# WGA_IR_P.net
KiCad netlist of a schematic drawn in Altium Designer
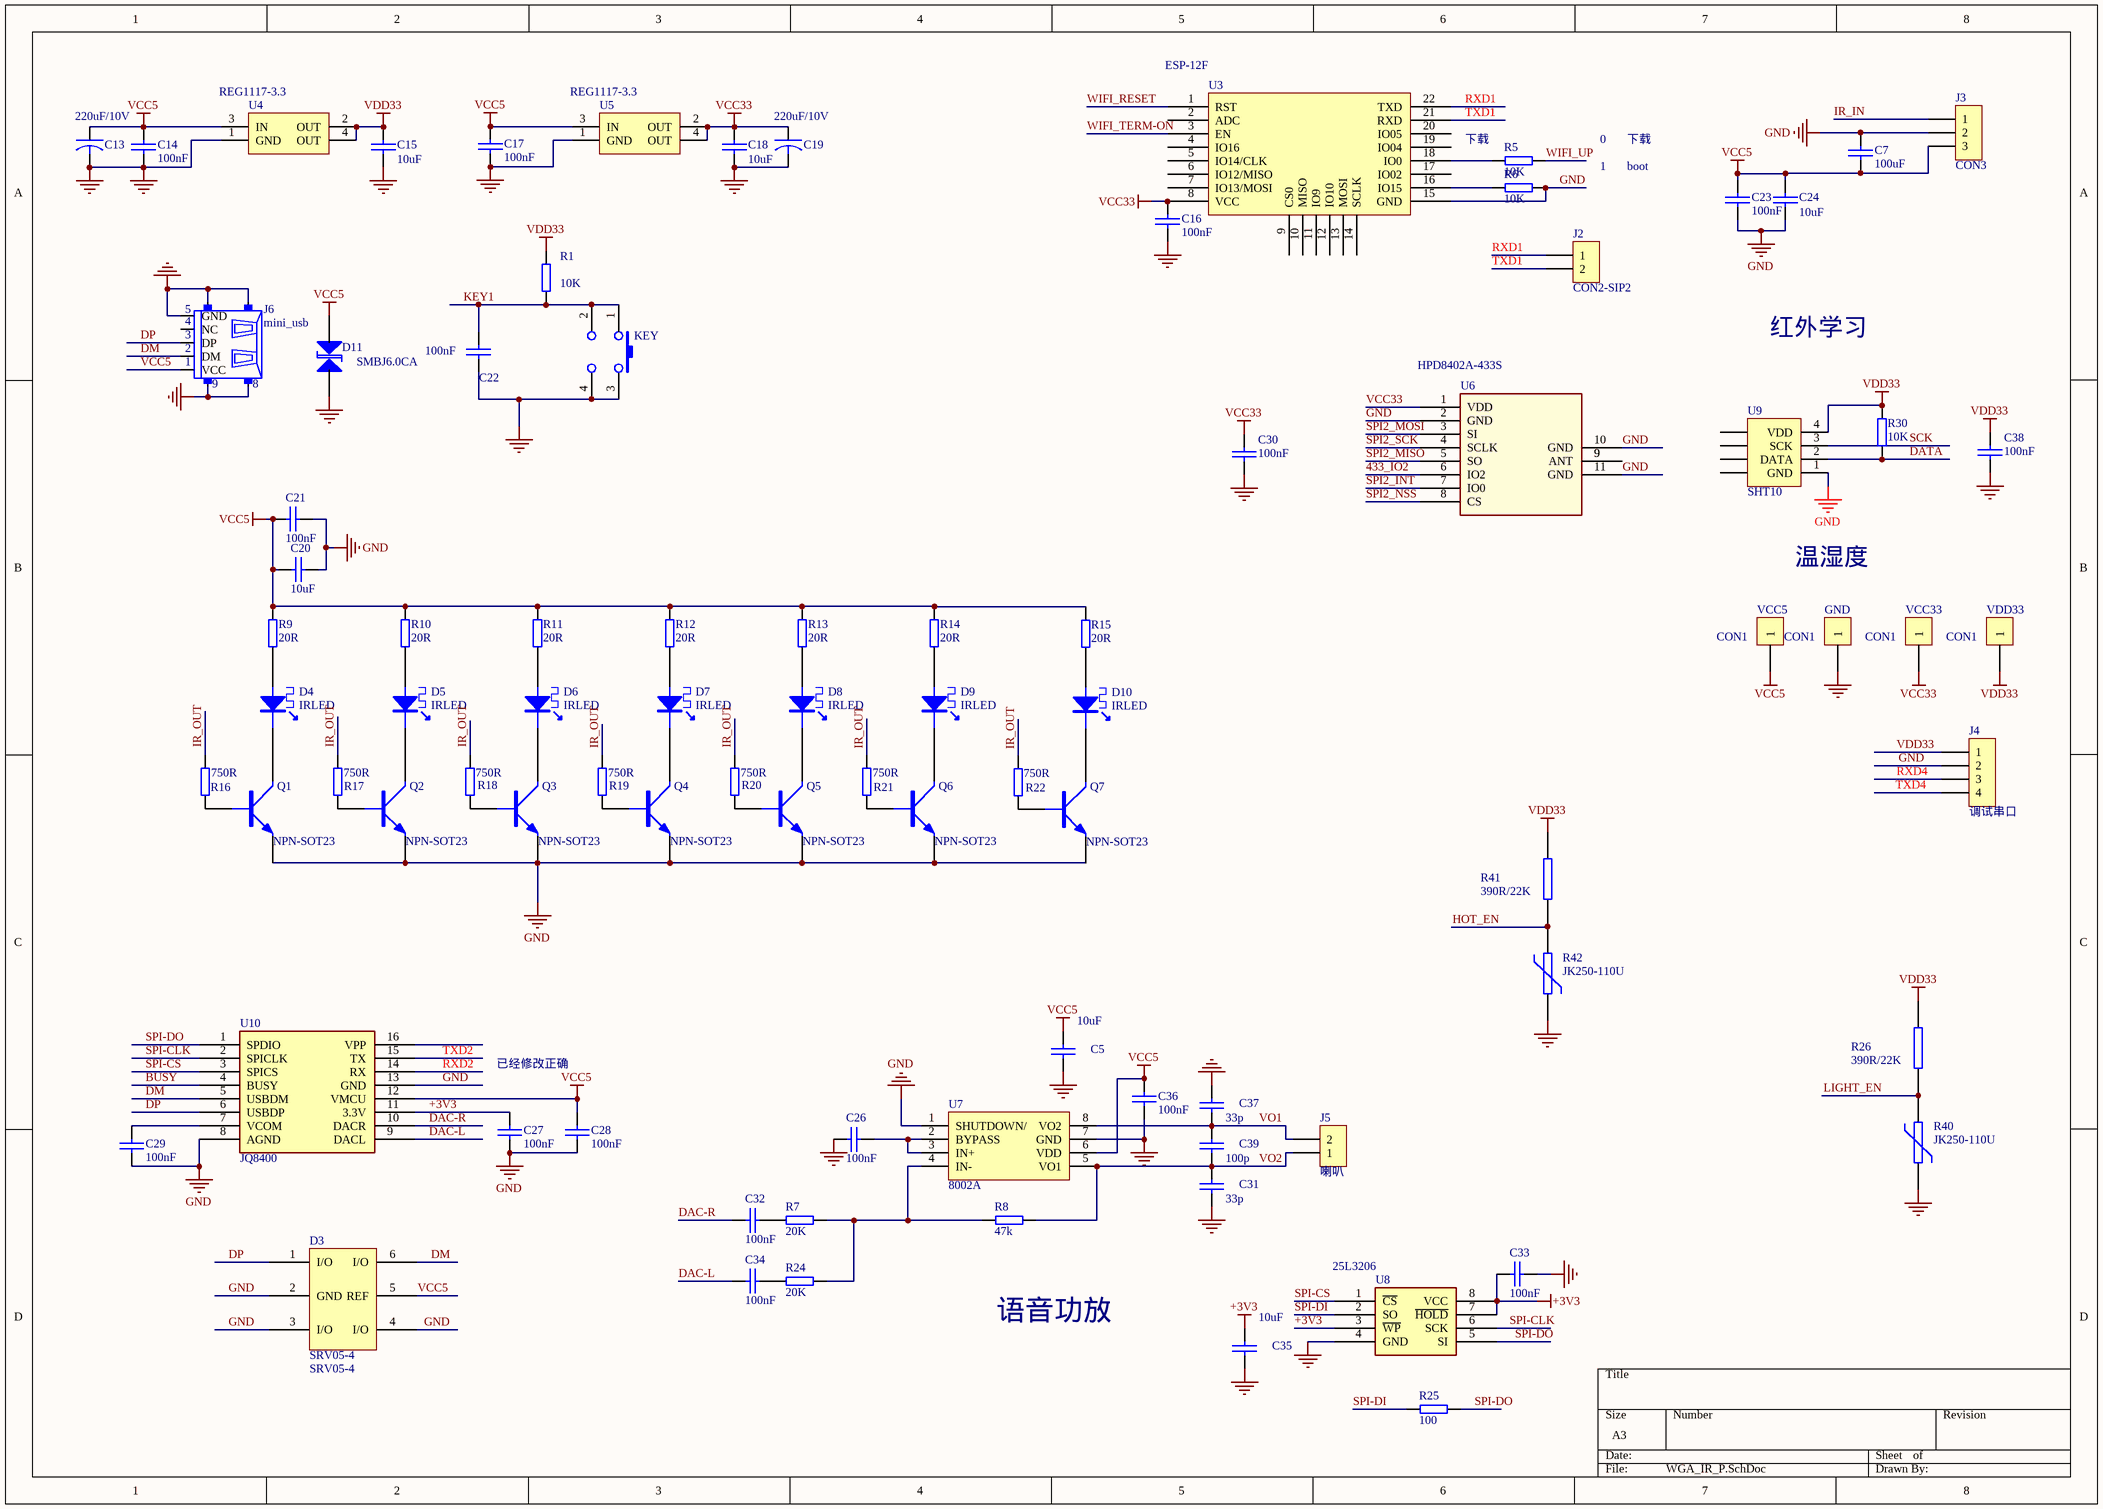
[diagram p0: WGA_IR_P.SchDoc]

(export (version "E")
  (design (tool "Eeschema 10.0.6"))
  (components
    (comp (ref "C5")
      (value "10uF")
      (footprint "C0805")
      (description "CAP CER 10UF 10V Y5V 0805")
      (fields
        (field (name "MANUFACTURER") "Yageo")
        (field (name "MANUFACTURER PART NUMBER") "CC0805ZKY5V6BB106")
      )
      (libsource (lib "电容") (part "C0805_10uF"))
    )
    (comp (ref "C7")
      (value "100uF")
      (footprint "C0603")
      (description "CAP CER 100PF 50V 5% NPO 0603")
      (fields
        (field (name "MANUFACTURER") "Yageo")
        (field (name "MANUFACTURER PART NUMBER") "CC0603JRNPO9BN101")
      )
      (libsource (lib "电容") (part "C0603_100p"))
    )
    (comp (ref "C13")
      (value "220uF/10V")
      (footprint "C6032")
      (description "CAP TANT 220UF 10V 10% 2312")
      (fields
        (field (name "MANUFACTURER") "AVX Corporation")
        (field (name "MANUFACTURER PART NUMBER") "TAJC227K010RNJ")
      )
      (libsource (lib "红外微波探测") (part "C6032_220uF_10V"))
    )
    (comp (ref "C14")
      (value "100nF")
      (footprint "C0603")
      (description "CAP CER 0.1UF 50V Y5V 0603")
      (fields
        (field (name "MANUFACTURER") "Yageo")
        (field (name "MANUFACTURER PART NUMBER") "CC0603ZRY5V9BB104")
      )
      (libsource (lib "电容") (part "C0603_100nF"))
    )
    (comp (ref "C15")
      (value "10uF")
      (footprint "C0805")
      (description "CAP CER 10UF 10V Y5V 0805")
      (fields
        (field (name "MANUFACTURER") "Yageo")
        (field (name "MANUFACTURER PART NUMBER") "CC0805ZKY5V6BB106")
      )
      (libsource (lib "电容") (part "C0805_10uF"))
    )
    (comp (ref "C16")
      (value "100nF")
      (footprint "C0603")
      (description "CAP CER 0.1UF 50V Y5V 0603")
      (fields
        (field (name "MANUFACTURER") "Yageo")
        (field (name "MANUFACTURER PART NUMBER") "CC0603ZRY5V9BB104")
      )
      (libsource (lib "电容") (part "C0603_100nF"))
    )
    (comp (ref "C17")
      (value "100nF")
      (footprint "C0603")
      (description "CAP CER 0.1UF 50V Y5V 0603")
      (fields
        (field (name "MANUFACTURER") "Yageo")
        (field (name "MANUFACTURER PART NUMBER") "CC0603ZRY5V9BB104")
      )
      (libsource (lib "电容") (part "C0603_100nF"))
    )
    (comp (ref "C18")
      (value "10uF")
      (footprint "C0805")
      (description "CAP CER 10UF 10V Y5V 0805")
      (fields
        (field (name "MANUFACTURER") "Yageo")
        (field (name "MANUFACTURER PART NUMBER") "CC0805ZKY5V6BB106")
      )
      (libsource (lib "电容") (part "C0805_10uF"))
    )
    (comp (ref "C19")
      (value "220uF/10V")
      (footprint "C6032")
      (description "CAP TANT 220UF 10V 10% 2312")
      (fields
        (field (name "MANUFACTURER") "AVX Corporation")
        (field (name "MANUFACTURER PART NUMBER") "TAJC227K010RNJ")
      )
      (libsource (lib "红外微波探测") (part "C6032_220uF_10V"))
    )
    (comp (ref "C20")
      (value "10uF")
      (footprint "C0805")
      (description "CAP CER 10UF 10V Y5V 0805")
      (fields
        (field (name "MANUFACTURER") "Yageo")
        (field (name "MANUFACTURER PART NUMBER") "CC0805ZKY5V6BB106")
      )
      (libsource (lib "电容") (part "C0805_10uF"))
    )
    (comp (ref "C21")
      (value "100nF")
      (footprint "C0603")
      (description "CAP CER 0.1UF 50V Y5V 0603")
      (fields
        (field (name "MANUFACTURER") "Yageo")
        (field (name "MANUFACTURER PART NUMBER") "CC0603ZRY5V9BB104")
      )
      (libsource (lib "电容") (part "C0603_100nF"))
    )
    (comp (ref "C22")
      (value "100nF")
      (footprint "C0603")
      (description "CAP CER 0.1UF 50V Y5V 0603")
      (fields
        (field (name "MANUFACTURER") "Yageo")
        (field (name "MANUFACTURER PART NUMBER") "CC0603ZRY5V9BB104")
      )
      (libsource (lib "电容") (part "C0603_100nF"))
    )
    (comp (ref "C23")
      (value "100nF")
      (footprint "C0603")
      (description "CAP CER 0.1UF 50V Y5V 0603")
      (fields
        (field (name "MANUFACTURER") "Yageo")
        (field (name "MANUFACTURER PART NUMBER") "CC0603ZRY5V9BB104")
      )
      (libsource (lib "电容") (part "C0603_100nF"))
    )
    (comp (ref "C24")
      (value "10uF")
      (footprint "C0805")
      (description "CAP CER 10UF 10V Y5V 0805")
      (fields
        (field (name "MANUFACTURER") "Yageo")
        (field (name "MANUFACTURER PART NUMBER") "CC0805ZKY5V6BB106")
      )
      (libsource (lib "电容") (part "C0805_10uF"))
    )
    (comp (ref "C26")
      (value "100nF")
      (footprint "C0603")
      (description "CAP CER 0.1UF 50V Y5V 0603")
      (fields
        (field (name "MANUFACTURER") "Yageo")
        (field (name "MANUFACTURER PART NUMBER") "CC0603ZRY5V9BB104")
      )
      (libsource (lib "电容") (part "C0603_100nF"))
    )
    (comp (ref "C27")
      (value "100nF")
      (footprint "C0603")
      (description "CAP CER 0.1UF 50V Y5V 0603")
      (fields
        (field (name "MANUFACTURER") "Yageo")
        (field (name "MANUFACTURER PART NUMBER") "CC0603ZRY5V9BB104")
      )
      (libsource (lib "电容") (part "C0603_100nF"))
    )
    (comp (ref "C28")
      (value "100nF")
      (footprint "C0603")
      (description "CAP CER 0.1UF 50V Y5V 0603")
      (fields
        (field (name "MANUFACTURER") "Yageo")
        (field (name "MANUFACTURER PART NUMBER") "CC0603ZRY5V9BB104")
      )
      (libsource (lib "电容") (part "C0603_100nF"))
    )
    (comp (ref "C29")
      (value "100nF")
      (footprint "C0603")
      (description "CAP CER 0.1UF 50V Y5V 0603")
      (fields
        (field (name "MANUFACTURER") "Yageo")
        (field (name "MANUFACTURER PART NUMBER") "CC0603ZRY5V9BB104")
      )
      (libsource (lib "电容") (part "C0603_100nF"))
    )
    (comp (ref "C30")
      (value "100nF")
      (footprint "C0603")
      (description "CAP CER 0.1UF 50V Y5V 0603")
      (fields
        (field (name "MANUFACTURER") "Yageo")
        (field (name "MANUFACTURER PART NUMBER") "CC0603ZRY5V9BB104")
      )
      (libsource (lib "电容") (part "C0603_100nF"))
    )
    (comp (ref "C31")
      (value "33p")
      (footprint "C0603")
      (description "CAP CER 33PF 50V 5% NPO 0603")
      (fields
        (field (name "MANUFACTURER") "Yageo")
        (field (name "MANUFACTURER PART NUMBER") "CC0603JRNPO9BN330")
      )
      (libsource (lib "红外微波探测") (part "C0603_33p"))
    )
    (comp (ref "C32")
      (value "100nF")
      (footprint "C0603")
      (description "CAP CER 0.1UF 50V Y5V 0603")
      (fields
        (field (name "MANUFACTURER") "Yageo")
        (field (name "MANUFACTURER PART NUMBER") "CC0603ZRY5V9BB104")
      )
      (libsource (lib "电容") (part "C0603_100nF"))
    )
    (comp (ref "C33")
      (value "100nF")
      (footprint "C0603")
      (description "CAP CER 0.1UF 50V Y5V 0603")
      (fields
        (field (name "MANUFACTURER") "Yageo")
        (field (name "MANUFACTURER PART NUMBER") "CC0603ZRY5V9BB104")
      )
      (libsource (lib "电容") (part "C0603_100nF"))
    )
    (comp (ref "C34")
      (value "100nF")
      (footprint "C0603")
      (description "CAP CER 0.1UF 50V Y5V 0603")
      (fields
        (field (name "MANUFACTURER") "Yageo")
        (field (name "MANUFACTURER PART NUMBER") "CC0603ZRY5V9BB104")
      )
      (libsource (lib "电容") (part "C0603_100nF"))
    )
    (comp (ref "C35")
      (value "10uF")
      (footprint "C0805")
      (description "CAP CER 10UF 10V Y5V 0805")
      (fields
        (field (name "MANUFACTURER") "Yageo")
        (field (name "MANUFACTURER PART NUMBER") "CC0805ZKY5V6BB106")
      )
      (libsource (lib "电容") (part "C0805_10uF"))
    )
    (comp (ref "C36")
      (value "100nF")
      (footprint "C0603")
      (description "CAP CER 0.1UF 50V Y5V 0603")
      (fields
        (field (name "MANUFACTURER") "Yageo")
        (field (name "MANUFACTURER PART NUMBER") "CC0603ZRY5V9BB104")
      )
      (libsource (lib "电容") (part "C0603_100nF"))
    )
    (comp (ref "C37")
      (value "33p")
      (footprint "C0603")
      (description "CAP CER 33PF 50V 5% NPO 0603")
      (fields
        (field (name "MANUFACTURER") "Yageo")
        (field (name "MANUFACTURER PART NUMBER") "CC0603JRNPO9BN330")
      )
      (libsource (lib "红外微波探测") (part "C0603_33p"))
    )
    (comp (ref "C38")
      (value "100nF")
      (footprint "C0603")
      (description "CAP CER 0.1UF 50V Y5V 0603")
      (fields
        (field (name "MANUFACTURER") "Yageo")
        (field (name "MANUFACTURER PART NUMBER") "CC0603ZRY5V9BB104")
      )
      (libsource (lib "电容") (part "C0603_100nF"))
    )
    (comp (ref "C39")
      (value "100p")
      (footprint "C0603")
      (description "CAP CER 100PF 50V 5% NPO 0603")
      (fields
        (field (name "MANUFACTURER") "Yageo")
        (field (name "MANUFACTURER PART NUMBER") "CC0603JRNPO9BN101")
      )
      (libsource (lib "红外微波探测") (part "C0603_100p"))
    )
    (comp (ref "D3")
      (value "SRV05-4")
      (footprint "SRV05-4")
      (description "TVS SOT-26")
      (fields (field (name "ALTIUM_VALUE") "SRV05-4"))
      (libsource (lib "二极管") (part "SRV05-4"))
    )
    (comp (ref "D4") (value "IRLED") (footprint "T1-5MM - 2N") (libsource (lib "二极管") (part "IRLED")))
    (comp (ref "D5") (value "IRLED") (footprint "T1-5MM - 2N") (libsource (lib "二极管") (part "IRLED")))
    (comp (ref "D6") (value "IRLED") (footprint "T1-5MM - 2N") (libsource (lib "二极管") (part "IRLED")))
    (comp (ref "D7") (value "IRLED") (footprint "T1-5MM - 2N") (libsource (lib "二极管") (part "IRLED")))
    (comp (ref "D8") (value "IRLED") (footprint "T1-5MM - 2N") (libsource (lib "二极管") (part "IRLED")))
    (comp (ref "D9") (value "IRLED") (footprint "T1-5MM - 2N") (libsource (lib "二极管") (part "IRLED")))
    (comp (ref "D10") (value "IRLED") (footprint "T1-5MM - 2N") (libsource (lib "二极管") (part "IRLED")))
    (comp (ref "D11")
      (value "SMBJ6.0CA")
      (footprint "D3528")
      (description "TVS DIODE 6VWM 10.3VC SMB")
      (fields (field (name "MANUFACTURER") "Littelfuse Inc"))
      (libsource (lib "二极管") (part "D3528_TVS_6.0"))
    )
    (comp (ref "GND")
      (value "CON1")
      (footprint "PAD")
      (description "Connector")
      (libsource (lib "接插件") (part "CON1"))
    )
    (comp (ref "J2")
      (value "CON2-SIP2")
      (footprint "SIP2")
      (description "Connector")
      (libsource (lib "接插件") (part "CON2-SIP2"))
    )
    (comp (ref "J3")
      (value "CON3")
      (footprint "TO-92C")
      (description "Connector")
      (libsource (lib "接插件") (part "CON3"))
    )
    (comp (ref "J4")
      (value "调试串口")
      (footprint "SIP4")
      (description "2.54mm dip")
      (libsource (lib "接插件") (part "CON4"))
    )
    (comp (ref "J5")
      (value "喇叭")
      (footprint "加盖喇叭")
      (description "8欧 0.5w 直径10mm")
      (libsource (lib "接插件") (part "CON2"))
    )
    (comp (ref "J6")
      (value "mini_usb")
      (footprint "MICRO_USB-B")
      (description "CONN RECEPT MINIUSB R/A 5POS SMD")
      (fields
        (field (name "MANUFACTURER") "Molex Inc")
        (field (name "MANUFACTURER PART NUMBER") "0675031020")
      )
      (libsource (lib "红外微波探测") (part "MINI_USB"))
    )
    (comp (ref "KEY") (value "SW-PB 4") (footprint "SWITCH(6*6*7)") (libsource (lib "接插件") (part "SW-PB 4")))
    (comp (ref "Q1")
      (value "NPN-SOT23")
      (footprint "SOT23")
      (description "NPN Transistor")
      (libsource (lib "三极管") (part "NPN-SOT23"))
    )
    (comp (ref "Q2")
      (value "NPN-SOT23")
      (footprint "SOT23")
      (description "NPN Transistor")
      (libsource (lib "三极管") (part "NPN-SOT23"))
    )
    (comp (ref "Q3")
      (value "NPN-SOT23")
      (footprint "SOT23")
      (description "NPN Transistor")
      (libsource (lib "三极管") (part "NPN-SOT23"))
    )
    (comp (ref "Q4")
      (value "NPN-SOT23")
      (footprint "SOT23")
      (description "NPN Transistor")
      (libsource (lib "三极管") (part "NPN-SOT23"))
    )
    (comp (ref "Q5")
      (value "NPN-SOT23")
      (footprint "SOT23")
      (description "NPN Transistor")
      (libsource (lib "三极管") (part "NPN-SOT23"))
    )
    (comp (ref "Q6")
      (value "NPN-SOT23")
      (footprint "SOT23")
      (description "NPN Transistor")
      (libsource (lib "三极管") (part "NPN-SOT23"))
    )
    (comp (ref "Q7")
      (value "NPN-SOT23")
      (footprint "SOT23")
      (description "NPN Transistor")
      (libsource (lib "三极管") (part "NPN-SOT23"))
    )
    (comp (ref "R1")
      (value "10K")
      (footprint "R0603")
      (description "RES 10K OHM 1/10W 5% 0603 SMD")
      (fields
        (field (name "MANUFACTURER") "Yageo")
        (field (name "MANUFACTURER PART NUMBER") "RC0603JR-0710KL")
      )
      (libsource (lib "电阻") (part "R0603_10K_5%"))
    )
    (comp (ref "R5")
      (value "10K")
      (footprint "R0603")
      (description "RES 10K OHM 1/10W 5% 0603 SMD")
      (fields
        (field (name "MANUFACTURER") "Yageo")
        (field (name "MANUFACTURER PART NUMBER") "RC0603JR-0710KL")
      )
      (libsource (lib "电阻") (part "R0603_10K_5%"))
    )
    (comp (ref "R6")
      (value "10K")
      (footprint "R0603")
      (description "RES 10K OHM 1/10W 5% 0603 SMD")
      (fields
        (field (name "MANUFACTURER") "Yageo")
        (field (name "MANUFACTURER PART NUMBER") "RC0603JR-0710KL")
      )
      (libsource (lib "电阻") (part "R0603_10K_5%"))
    )
    (comp (ref "R7")
      (value "20K")
      (footprint "R0603")
      (description "RES 20K OHM 1/10W 5% 0603 SMD")
      (fields
        (field (name "MANUFACTURER") "Yageo")
        (field (name "MANUFACTURER PART NUMBER") "RC0603JR-0720KL")
      )
      (libsource (lib "红外微波探测") (part "R0603_20K_5%"))
    )
    (comp (ref "R8")
      (value "47k")
      (footprint "R0603")
      (description "RES 47K OHM 1/10W 5% 0603 SMD")
      (fields
        (field (name "MANUFACTURER") "Yageo")
        (field (name "MANUFACTURER PART NUMBER") "RC0603JR-0747KL")
      )
      (libsource (lib "红外微波探测") (part "R0603_47K_5%"))
    )
    (comp (ref "R9")
      (value "20R")
      (footprint "R0603")
      (description "RES 470 OHM 1/10W 5% 0603 SMD")
      (fields
        (field (name "MANUFACTURER") "Yageo")
        (field (name "MANUFACTURER PART NUMBER") "RC0603JR-07470RL")
      )
      (libsource (lib "电阻") (part "R0603_470_5%"))
    )
    (comp (ref "R10")
      (value "20R")
      (footprint "R0603")
      (description "RES 470 OHM 1/10W 5% 0603 SMD")
      (fields
        (field (name "MANUFACTURER") "Yageo")
        (field (name "MANUFACTURER PART NUMBER") "RC0603JR-07470RL")
      )
      (libsource (lib "电阻") (part "R0603_470_5%"))
    )
    (comp (ref "R11")
      (value "20R")
      (footprint "R0603")
      (description "RES 470 OHM 1/10W 5% 0603 SMD")
      (fields
        (field (name "MANUFACTURER") "Yageo")
        (field (name "MANUFACTURER PART NUMBER") "RC0603JR-07470RL")
      )
      (libsource (lib "电阻") (part "R0603_470_5%"))
    )
    (comp (ref "R12")
      (value "20R")
      (footprint "R0603")
      (description "RES 470 OHM 1/10W 5% 0603 SMD")
      (fields
        (field (name "MANUFACTURER") "Yageo")
        (field (name "MANUFACTURER PART NUMBER") "RC0603JR-07470RL")
      )
      (libsource (lib "电阻") (part "R0603_470_5%"))
    )
    (comp (ref "R13")
      (value "20R")
      (footprint "R0603")
      (description "RES 470 OHM 1/10W 5% 0603 SMD")
      (fields
        (field (name "MANUFACTURER") "Yageo")
        (field (name "MANUFACTURER PART NUMBER") "RC0603JR-07470RL")
      )
      (libsource (lib "电阻") (part "R0603_470_5%"))
    )
    (comp (ref "R14")
      (value "20R")
      (footprint "R0603")
      (description "RES 470 OHM 1/10W 5% 0603 SMD")
      (fields
        (field (name "MANUFACTURER") "Yageo")
        (field (name "MANUFACTURER PART NUMBER") "RC0603JR-07470RL")
      )
      (libsource (lib "电阻") (part "R0603_470_5%"))
    )
    (comp (ref "R15")
      (value "20R")
      (footprint "R0603")
      (description "RES 470 OHM 1/10W 5% 0603 SMD")
      (fields
        (field (name "MANUFACTURER") "Yageo")
        (field (name "MANUFACTURER PART NUMBER") "RC0603JR-07470RL")
      )
      (libsource (lib "电阻") (part "R0603_470_5%"))
    )
    (comp (ref "R16")
      (value "750R")
      (footprint "R0603")
      (fields (field (name "MANUFACTURER") "Yageo") (field (name "Comment") "R0603"))
      (libsource (lib "电阻") (part "R0603"))
    )
    (comp (ref "R17")
      (value "750R")
      (footprint "R0603")
      (fields (field (name "MANUFACTURER") "Yageo") (field (name "Comment") "R0603"))
      (libsource (lib "电阻") (part "R0603"))
    )
    (comp (ref "R18")
      (value "750R")
      (footprint "R0603")
      (fields (field (name "MANUFACTURER") "Yageo") (field (name "Comment") "R0603"))
      (libsource (lib "电阻") (part "R0603"))
    )
    (comp (ref "R19")
      (value "750R")
      (footprint "R0603")
      (fields (field (name "MANUFACTURER") "Yageo") (field (name "Comment") "R0603"))
      (libsource (lib "电阻") (part "R0603"))
    )
    (comp (ref "R20")
      (value "750R")
      (footprint "R0603")
      (fields (field (name "MANUFACTURER") "Yageo") (field (name "Comment") "R0603"))
      (libsource (lib "电阻") (part "R0603"))
    )
    (comp (ref "R21")
      (value "750R")
      (footprint "R0603")
      (fields (field (name "MANUFACTURER") "Yageo") (field (name "Comment") "R0603"))
      (libsource (lib "电阻") (part "R0603"))
    )
    (comp (ref "R22")
      (value "750R")
      (footprint "R0603")
      (fields (field (name "MANUFACTURER") "Yageo") (field (name "Comment") "R0603"))
      (libsource (lib "电阻") (part "R0603"))
    )
    (comp (ref "R24")
      (value "20K")
      (footprint "R0603")
      (description "RES 20K OHM 1/10W 5% 0603 SMD")
      (fields
        (field (name "MANUFACTURER") "Yageo")
        (field (name "MANUFACTURER PART NUMBER") "RC0603JR-0720KL")
      )
      (libsource (lib "红外微波探测") (part "R0603_20K_5%"))
    )
    (comp (ref "R25")
      (value "100")
      (footprint "R0603")
      (description "RES 100 OHM 1/10W 5% 0603 SMD")
      (fields
        (field (name "MANUFACTURER") "Yageo")
        (field (name "MANUFACTURER PART NUMBER") "RC0603JR-07100RL")
      )
      (libsource (lib "红外微波探测") (part "R0603_100_5%"))
    )
    (comp (ref "R26")
      (value "390R/22K")
      (footprint "R0603")
      (description "贴片电阻")
      (libsource (lib "电阻") (part "RES-0805"))
    )
    (comp (ref "R30")
      (value "10K")
      (footprint "R0603")
      (description "RES 10K OHM 1/10W 5% 0603 SMD")
      (fields
        (field (name "MANUFACTURER") "Yageo")
        (field (name "MANUFACTURER PART NUMBER") "RC0603JR-0710KL")
      )
      (libsource (lib "电阻") (part "R0603_10K_5%"))
    )
    (comp (ref "R40") (value "JK250-110U") (footprint "JK250-110U") (libsource (lib "电阻") (part "PTC")))
    (comp (ref "R41")
      (value "390R/22K")
      (footprint "R0603")
      (description "贴片电阻")
      (libsource (lib "电阻") (part "RES-0805"))
    )
    (comp (ref "R42") (value "JK250-110U") (footprint "JK250-110U") (libsource (lib "电阻") (part "PTC")))
    (comp (ref "U3")
      (value "ESP-12F")
      (footprint "ESP-12F")
      (description "WIFI ESP-12F  ESP8266")
      (fields (field (name "MANUFACTURER") "安信可") (field (name "Comment") "ESP8266-12F"))
      (libsource (lib "模块组件") (part "ESP8266-12F"))
    )
    (comp (ref "U4")
      (value "REG1117-3.3")
      (footprint "SOT223")
      (description "IC REG LDO 3.3V 0.8A SOT223")
      (fields
        (field (name "MANUFACTURER") "Texas Instruments")
        (field (name "MANUFACTURER PART NUMBER") "REG1117-3.3/2K5")
      )
      (libsource (lib "红外微波探测") (part "REG1117-3.3"))
    )
    (comp (ref "U5")
      (value "REG1117-3.3")
      (footprint "SOT223")
      (description "IC REG LDO 3.3V 0.8A SOT223")
      (fields
        (field (name "MANUFACTURER") "Texas Instruments")
        (field (name "MANUFACTURER PART NUMBER") "REG1117-3.3/2K5")
      )
      (libsource (lib "红外微波探测") (part "REG1117-3.3"))
    )
    (comp (ref "U6")
      (value "HPD8402A-433S")
      (footprint "HPD8402A-433S")
      (description "RF TXRX MODULE CC1101 433Mhz")
      (fields (field (name "MANUFACTURER") "PDTeK(合普顿科技)"))
      (libsource (lib "模块组件") (part "HPD8402A-433S"))
    )
    (comp (ref "U7") (value "8002A") (footprint "SO8") (libsource (lib "IC") (part "LM4890")))
    (comp (ref "U8")
      (value "25L3206")
      (footprint "SSOP8")
      (description "IC FLASH 32MBIT 86MHZ 8SOP 32M (4M x 8)")
      (fields
        (field (name "MANUFACTURER") "Macronix")
        (field (name "MANUFACTURER PART NUMBER") "MX25L3206EM2I-12G")
      )
      (libsource (lib "红外微波探测") (part "25L3206"))
    )
    (comp (ref "U9")
      (value "SHT10")
      (footprint "SHT10")
      (description "贴片温湿度传感器SHT10")
      (libsource (lib "*") (part "SHT10"))
    )
    (comp (ref "U10")
      (value "JQ8400")
      (footprint "SOP16")
      (fields (field (name "MANUFACTURER") "深圳佳强电子科技有限公司"))
      (libsource (lib "集成电路") (part "JQ8400"))
    )
    (comp (ref "VCC5")
      (value "CON1")
      (footprint "PAD")
      (description "Connector")
      (libsource (lib "接插件") (part "CON1"))
    )
    (comp (ref "VCC33")
      (value "CON1")
      (footprint "PAD")
      (description "Connector")
      (libsource (lib "接插件") (part "CON1"))
    )
    (comp (ref "VDD33")
      (value "CON1")
      (footprint "PAD")
      (description "Connector")
      (libsource (lib "接插件") (part "CON1"))
    )
  )
  (nets
    (net (code "1") (name "+3V3") (class "Default")
      (node (ref "C27") (pin "1") (pinfunction "1_1") (pintype "passive"))
      (node (ref "C33") (pin "1") (pinfunction "1_1") (pintype "passive"))
      (node (ref "C35") (pin "1") (pinfunction "1_1") (pintype "passive"))
      (node (ref "U10") (pin "11") (pinfunction "3.3V_11") (pintype "passive"))
      (node (ref "U8") (pin "3") (pinfunction "~{WP}_3") (pintype "passive"))
      (node (ref "U8") (pin "7") (pinfunction "~{HOLD}_7") (pintype "passive"))
      (node (ref "U8") (pin "8") (pinfunction "VCC_8") (pintype "passive"))
    )
    (net (code "2") (name "/433_IO2") (class "Default")
      (node (ref "U6") (pin "6") (pinfunction "IO2_6") (pintype "passive"))
    )
    (net (code "3") (name "/BUSY") (class "Default")
      (node (ref "U10") (pin "4") (pinfunction "BUSY_4") (pintype "passive"))
    )
    (net (code "4") (name "/DAC-L") (class "Default")
      (node (ref "C34") (pin "2") (pinfunction "2_2") (pintype "passive"))
      (node (ref "U10") (pin "9") (pinfunction "DACL_9") (pintype "passive"))
    )
    (net (code "5") (name "/DAC-R") (class "Default")
      (node (ref "C32") (pin "2") (pinfunction "2_2") (pintype "passive"))
      (node (ref "U10") (pin "10") (pinfunction "DACR_10") (pintype "passive"))
    )
    (net (code "6") (name "/DATA") (class "Default")
      (node (ref "R30") (pin "1") (pinfunction "1_1") (pintype "passive"))
      (node (ref "U9") (pin "2") (pinfunction "DATA_2") (pintype "passive"))
    )
    (net (code "7") (name "/DM") (class "Default")
      (node (ref "D3") (pin "6") (pinfunction "I/O_6") (pintype "power_in"))
      (node (ref "J6") (pin "2") (pinfunction "DM_2") (pintype "passive"))
      (node (ref "U10") (pin "5") (pinfunction "USBDM_5") (pintype "passive"))
    )
    (net (code "8") (name "/DP") (class "Default")
      (node (ref "D3") (pin "1") (pinfunction "I/O_1") (pintype "passive"))
      (node (ref "J6") (pin "3") (pinfunction "DP_3") (pintype "passive"))
      (node (ref "U10") (pin "6") (pinfunction "USBDP_6") (pintype "passive"))
    )
    (net (code "9") (name "/HOT_EN") (class "Default")
      (node (ref "R41") (pin "1") (pinfunction "1_1") (pintype "passive"))
      (node (ref "R42") (pin "2") (pinfunction "2_2") (pintype "passive"))
    )
    (net (code "10") (name "/IR_IN") (class "Default")
      (node (ref "J3") (pin "1") (pinfunction "1_1") (pintype "passive"))
    )
    (net (code "11") (name "/IR_OUT") (class "Default")
      (node (ref "R16") (pin "2") (pinfunction "2_2") (pintype "passive"))
      (node (ref "R17") (pin "2") (pinfunction "2_2") (pintype "passive"))
      (node (ref "R18") (pin "2") (pinfunction "2_2") (pintype "passive"))
      (node (ref "R19") (pin "2") (pinfunction "2_2") (pintype "passive"))
      (node (ref "R20") (pin "2") (pinfunction "2_2") (pintype "passive"))
      (node (ref "R21") (pin "2") (pinfunction "2_2") (pintype "passive"))
      (node (ref "R22") (pin "2") (pinfunction "2_2") (pintype "passive"))
    )
    (net (code "12") (name "/KEY1") (class "Default")
      (node (ref "C22") (pin "1") (pinfunction "1_1") (pintype "passive"))
      (node (ref "KEY") (pin "1") (pinfunction "1_1") (pintype "passive"))
      (node (ref "KEY") (pin "2") (pinfunction "2_2") (pintype "passive"))
      (node (ref "R1") (pin "2") (pinfunction "2_2") (pintype "passive"))
    )
    (net (code "13") (name "/LIGHT_EN") (class "Default")
      (node (ref "R26") (pin "1") (pinfunction "1_1") (pintype "passive"))
      (node (ref "R40") (pin "2") (pinfunction "2_2") (pintype "passive"))
    )
    (net (code "14") (name "/RXD1") (class "Default")
      (node (ref "J2") (pin "1") (pinfunction "1_1") (pintype "passive"))
      (node (ref "U3") (pin "22") (pinfunction "TXD_22") (pintype "passive"))
    )
    (net (code "15") (name "/RXD2") (class "Default")
      (node (ref "U10") (pin "14") (pinfunction "RX_14") (pintype "passive"))
    )
    (net (code "16") (name "/RXD4") (class "Default")
      (node (ref "J4") (pin "3") (pinfunction "3_3") (pintype "passive"))
    )
    (net (code "17") (name "/SCK") (class "Default")
      (node (ref "U9") (pin "3") (pinfunction "SCK_3") (pintype "passive"))
    )
    (net (code "18") (name "/SPI-CLK") (class "Default")
      (node (ref "U10") (pin "2") (pinfunction "SPICLK_2") (pintype "passive"))
      (node (ref "U8") (pin "6") (pinfunction "SCK_6") (pintype "passive"))
    )
    (net (code "19") (name "/SPI-CS") (class "Default")
      (node (ref "U10") (pin "3") (pinfunction "SPICS_3") (pintype "passive"))
      (node (ref "U8") (pin "1") (pinfunction "~{CS}_1") (pintype "passive"))
    )
    (net (code "20") (name "/SPI-DI") (class "Default")
      (node (ref "R25") (pin "1") (pinfunction "1_1") (pintype "passive"))
      (node (ref "U8") (pin "2") (pinfunction "SO_2") (pintype "passive"))
    )
    (net (code "21") (name "/SPI-DO") (class "Default")
      (node (ref "R25") (pin "2") (pinfunction "2_2") (pintype "passive"))
      (node (ref "U10") (pin "1") (pinfunction "SPDIO_1") (pintype "passive"))
      (node (ref "U8") (pin "5") (pinfunction "SI_5") (pintype "passive"))
    )
    (net (code "22") (name "/SPI2_INT") (class "Default")
      (node (ref "U6") (pin "7") (pinfunction "IO0_7") (pintype "passive"))
    )
    (net (code "23") (name "/SPI2_MISO") (class "Default")
      (node (ref "U6") (pin "5") (pinfunction "SO_5") (pintype "passive"))
    )
    (net (code "24") (name "/SPI2_MOSI") (class "Default")
      (node (ref "U6") (pin "3") (pinfunction "SI_3") (pintype "passive"))
    )
    (net (code "25") (name "/SPI2_NSS") (class "Default")
      (node (ref "U6") (pin "8") (pinfunction "CS_8") (pintype "passive"))
    )
    (net (code "26") (name "/SPI2_SCK") (class "Default")
      (node (ref "U6") (pin "4") (pinfunction "SCLK_4") (pintype "passive"))
    )
    (net (code "27") (name "/TXD1") (class "Default")
      (node (ref "J2") (pin "2") (pinfunction "2_2") (pintype "passive"))
      (node (ref "U3") (pin "21") (pinfunction "RXD_21") (pintype "passive"))
    )
    (net (code "28") (name "/TXD2") (class "Default")
      (node (ref "U10") (pin "15") (pinfunction "TX_15") (pintype "passive"))
    )
    (net (code "29") (name "/TXD4") (class "Default")
      (node (ref "J4") (pin "4") (pinfunction "4_4") (pintype "passive"))
    )
    (net (code "30") (name "/VO1") (class "Default")
      (node (ref "C37") (pin "2") (pinfunction "2_2") (pintype "passive"))
      (node (ref "C39") (pin "1") (pinfunction "1_1") (pintype "passive"))
      (node (ref "J5") (pin "2") (pinfunction "2_2") (pintype "passive"))
      (node (ref "U7") (pin "8") (pinfunction "VO2_8") (pintype "passive"))
    )
    (net (code "31") (name "/VO2") (class "Default")
      (node (ref "C31") (pin "1") (pinfunction "1_1") (pintype "passive"))
      (node (ref "C39") (pin "2") (pinfunction "2_2") (pintype "passive"))
      (node (ref "J5") (pin "1") (pinfunction "1_1") (pintype "passive"))
      (node (ref "R8") (pin "2") (pinfunction "2_2") (pintype "passive"))
      (node (ref "U7") (pin "5") (pinfunction "VO1_5") (pintype "passive"))
    )
    (net (code "32") (name "/WIFI_RESET") (class "Default")
      (node (ref "U3") (pin "1") (pinfunction "RST_1") (pintype "passive"))
    )
    (net (code "33") (name "/WIFI_TERM-ON") (class "Default")
      (node (ref "U3") (pin "3") (pinfunction "EN_3") (pintype "passive"))
    )
    (net (code "34") (name "/WIFI_UP") (class "Default")
      (node (ref "R5") (pin "1") (pinfunction "1_1") (pintype "passive"))
    )
    (net (code "35") (name "GND") (class "Default")
      (node (ref "C13") (pin "2") (pinfunction "2_2") (pintype "passive"))
      (node (ref "C14") (pin "1") (pinfunction "1_1") (pintype "passive"))
      (node (ref "C15") (pin "2") (pinfunction "2_2") (pintype "passive"))
      (node (ref "C16") (pin "2") (pinfunction "2_2") (pintype "passive"))
      (node (ref "C17") (pin "1") (pinfunction "1_1") (pintype "passive"))
      (node (ref "C18") (pin "2") (pinfunction "2_2") (pintype "passive"))
      (node (ref "C19") (pin "2") (pinfunction "2_2") (pintype "passive"))
      (node (ref "C20") (pin "2") (pinfunction "2_2") (pintype "passive"))
      (node (ref "C21") (pin "2") (pinfunction "2_2") (pintype "passive"))
      (node (ref "C22") (pin "2") (pinfunction "2_2") (pintype "passive"))
      (node (ref "C23") (pin "2") (pinfunction "2_2") (pintype "passive"))
      (node (ref "C24") (pin "2") (pinfunction "2_2") (pintype "passive"))
      (node (ref "C26") (pin "2") (pinfunction "2_2") (pintype "passive"))
      (node (ref "C27") (pin "2") (pinfunction "2_2") (pintype "passive"))
      (node (ref "C28") (pin "2") (pinfunction "2_2") (pintype "passive"))
      (node (ref "C29") (pin "1") (pinfunction "1_1") (pintype "passive"))
      (node (ref "C30") (pin "2") (pinfunction "2_2") (pintype "passive"))
      (node (ref "C31") (pin "2") (pinfunction "2_2") (pintype "passive"))
      (node (ref "C33") (pin "2") (pinfunction "2_2") (pintype "passive"))
      (node (ref "C35") (pin "2") (pinfunction "2_2") (pintype "passive"))
      (node (ref "C36") (pin "1") (pinfunction "1_1") (pintype "passive"))
      (node (ref "C37") (pin "1") (pinfunction "1_1") (pintype "passive"))
      (node (ref "C38") (pin "2") (pinfunction "2_2") (pintype "passive"))
      (node (ref "C5") (pin "2") (pinfunction "2_2") (pintype "passive"))
      (node (ref "C7") (pin "2") (pinfunction "2_2") (pintype "passive"))
      (node (ref "D11") (pin "1") (pinfunction "1_1") (pintype "passive"))
      (node (ref "D3") (pin "2") (pinfunction "GND_2") (pintype "power_in"))
      (node (ref "D3") (pin "3") (pinfunction "I/O_3") (pintype "power_in"))
      (node (ref "D3") (pin "4") (pinfunction "I/O_4") (pintype "power_in"))
      (node (ref "GND") (pin "1") (pinfunction "1_1") (pintype "passive"))
      (node (ref "J3") (pin "2") (pinfunction "2_2") (pintype "passive"))
      (node (ref "J4") (pin "2") (pinfunction "2_2") (pintype "passive"))
      (node (ref "J6") (pin "5") (pinfunction "GND_5") (pintype "passive"))
      (node (ref "J6") (pin "6") (pinfunction "6_6") (pintype "passive"))
      (node (ref "J6") (pin "7") (pinfunction "7_7") (pintype "passive"))
      (node (ref "J6") (pin "8") (pinfunction "8_8") (pintype "passive"))
      (node (ref "J6") (pin "9") (pinfunction "9_9") (pintype "passive"))
      (node (ref "KEY") (pin "3") (pinfunction "3_3") (pintype "passive"))
      (node (ref "KEY") (pin "4") (pinfunction "4_4") (pintype "passive"))
      (node (ref "Q1") (pin "2") (pinfunction "E_2") (pintype "passive"))
      (node (ref "Q2") (pin "2") (pinfunction "E_2") (pintype "passive"))
      (node (ref "Q3") (pin "2") (pinfunction "E_2") (pintype "passive"))
      (node (ref "Q4") (pin "2") (pinfunction "E_2") (pintype "passive"))
      (node (ref "Q5") (pin "2") (pinfunction "E_2") (pintype "passive"))
      (node (ref "Q6") (pin "2") (pinfunction "E_2") (pintype "passive"))
      (node (ref "Q7") (pin "2") (pinfunction "E_2") (pintype "passive"))
      (node (ref "R40") (pin "1") (pinfunction "1_1") (pintype "passive"))
      (node (ref "R42") (pin "1") (pinfunction "1_1") (pintype "passive"))
      (node (ref "R6") (pin "1") (pinfunction "1_1") (pintype "passive"))
      (node (ref "U10") (pin "13") (pinfunction "GND_13") (pintype "passive"))
      (node (ref "U10") (pin "8") (pinfunction "AGND_8") (pintype "passive"))
      (node (ref "U3") (pin "15") (pinfunction "GND_15") (pintype "passive"))
      (node (ref "U4") (pin "1") (pinfunction "GND_1") (pintype "tri_state"))
      (node (ref "U5") (pin "1") (pinfunction "GND_1") (pintype "tri_state"))
      (node (ref "U6") (pin "10") (pinfunction "GND_10") (pintype "passive"))
      (node (ref "U6") (pin "11") (pinfunction "GND_11") (pintype "passive"))
      (node (ref "U6") (pin "2") (pinfunction "GND_2") (pintype "passive"))
      (node (ref "U7") (pin "1") (pinfunction "SHUTDOWN/_1") (pintype "passive"))
      (node (ref "U7") (pin "7") (pinfunction "GND_7") (pintype "passive"))
      (node (ref "U8") (pin "4") (pinfunction "GND_4") (pintype "passive"))
      (node (ref "U9") (pin "1") (pinfunction "GND_1") (pintype "passive"))
    )
    (net (code "36") (name "Net-(C32-Pad1)") (class "Default")
      (node (ref "C32") (pin "1") (pinfunction "1_1") (pintype "passive"))
      (node (ref "R7") (pin "2") (pinfunction "2_2") (pintype "passive"))
    )
    (net (code "37") (name "Net-(C34-Pad1)") (class "Default")
      (node (ref "C34") (pin "1") (pinfunction "1_1") (pintype "passive"))
      (node (ref "R24") (pin "2") (pinfunction "2_2") (pintype "passive"))
    )
    (net (code "38") (name "Net-(D4-Pad1)") (class "Default")
      (node (ref "D4") (pin "1") (pinfunction "1_1") (pintype "passive"))
      (node (ref "R9") (pin "1") (pinfunction "1_1") (pintype "passive"))
    )
    (net (code "39") (name "Net-(D5-Pad1)") (class "Default")
      (node (ref "D5") (pin "1") (pinfunction "1_1") (pintype "passive"))
      (node (ref "R10") (pin "1") (pinfunction "1_1") (pintype "passive"))
    )
    (net (code "40") (name "Net-(D6-Pad1)") (class "Default")
      (node (ref "D6") (pin "1") (pinfunction "1_1") (pintype "passive"))
      (node (ref "R11") (pin "1") (pinfunction "1_1") (pintype "passive"))
    )
    (net (code "41") (name "Net-(D7-Pad1)") (class "Default")
      (node (ref "D7") (pin "1") (pinfunction "1_1") (pintype "passive"))
      (node (ref "R12") (pin "1") (pinfunction "1_1") (pintype "passive"))
    )
    (net (code "42") (name "Net-(D8-Pad1)") (class "Default")
      (node (ref "D8") (pin "1") (pinfunction "1_1") (pintype "passive"))
      (node (ref "R13") (pin "1") (pinfunction "1_1") (pintype "passive"))
    )
    (net (code "43") (name "Net-(D9-Pad1)") (class "Default")
      (node (ref "D9") (pin "1") (pinfunction "1_1") (pintype "passive"))
      (node (ref "R14") (pin "1") (pinfunction "1_1") (pintype "passive"))
    )
    (net (code "44") (name "Net-(D10-Pad1)") (class "Default")
      (node (ref "D10") (pin "1") (pinfunction "1_1") (pintype "passive"))
      (node (ref "R15") (pin "1") (pinfunction "1_1") (pintype "passive"))
    )
    (net (code "45") (name "Net-(Q1-B)") (class "Default")
      (node (ref "Q1") (pin "1") (pinfunction "B_1") (pintype "passive"))
      (node (ref "R16") (pin "1") (pinfunction "1_1") (pintype "passive"))
    )
    (net (code "46") (name "Net-(Q1-C)") (class "Default")
      (node (ref "D4") (pin "2") (pinfunction "2_2") (pintype "passive"))
      (node (ref "Q1") (pin "3") (pinfunction "C_3") (pintype "passive"))
    )
    (net (code "47") (name "Net-(Q2-B)") (class "Default")
      (node (ref "Q2") (pin "1") (pinfunction "B_1") (pintype "passive"))
      (node (ref "R17") (pin "1") (pinfunction "1_1") (pintype "passive"))
    )
    (net (code "48") (name "Net-(Q2-C)") (class "Default")
      (node (ref "D5") (pin "2") (pinfunction "2_2") (pintype "passive"))
      (node (ref "Q2") (pin "3") (pinfunction "C_3") (pintype "passive"))
    )
    (net (code "49") (name "Net-(Q3-B)") (class "Default")
      (node (ref "Q3") (pin "1") (pinfunction "B_1") (pintype "passive"))
      (node (ref "R18") (pin "1") (pinfunction "1_1") (pintype "passive"))
    )
    (net (code "50") (name "Net-(Q3-C)") (class "Default")
      (node (ref "D6") (pin "2") (pinfunction "2_2") (pintype "passive"))
      (node (ref "Q3") (pin "3") (pinfunction "C_3") (pintype "passive"))
    )
    (net (code "51") (name "Net-(Q4-B)") (class "Default")
      (node (ref "Q4") (pin "1") (pinfunction "B_1") (pintype "passive"))
      (node (ref "R19") (pin "1") (pinfunction "1_1") (pintype "passive"))
    )
    (net (code "52") (name "Net-(Q4-C)") (class "Default")
      (node (ref "D7") (pin "2") (pinfunction "2_2") (pintype "passive"))
      (node (ref "Q4") (pin "3") (pinfunction "C_3") (pintype "passive"))
    )
    (net (code "53") (name "Net-(Q5-B)") (class "Default")
      (node (ref "Q5") (pin "1") (pinfunction "B_1") (pintype "passive"))
      (node (ref "R20") (pin "1") (pinfunction "1_1") (pintype "passive"))
    )
    (net (code "54") (name "Net-(Q5-C)") (class "Default")
      (node (ref "D8") (pin "2") (pinfunction "2_2") (pintype "passive"))
      (node (ref "Q5") (pin "3") (pinfunction "C_3") (pintype "passive"))
    )
    (net (code "55") (name "Net-(Q6-B)") (class "Default")
      (node (ref "Q6") (pin "1") (pinfunction "B_1") (pintype "passive"))
      (node (ref "R21") (pin "1") (pinfunction "1_1") (pintype "passive"))
    )
    (net (code "56") (name "Net-(Q6-C)") (class "Default")
      (node (ref "D9") (pin "2") (pinfunction "2_2") (pintype "passive"))
      (node (ref "Q6") (pin "3") (pinfunction "C_3") (pintype "passive"))
    )
    (net (code "57") (name "Net-(Q7-B)") (class "Default")
      (node (ref "Q7") (pin "1") (pinfunction "B_1") (pintype "passive"))
      (node (ref "R22") (pin "1") (pinfunction "1_1") (pintype "passive"))
    )
    (net (code "58") (name "Net-(Q7-C)") (class "Default")
      (node (ref "D10") (pin "2") (pinfunction "2_2") (pintype "passive"))
      (node (ref "Q7") (pin "3") (pinfunction "C_3") (pintype "passive"))
    )
    (net (code "59") (name "Net-(U3-IO0)") (class "Default")
      (node (ref "R5") (pin "2") (pinfunction "2_2") (pintype "passive"))
      (node (ref "U3") (pin "18") (pinfunction "IO0_18") (pintype "passive"))
    )
    (net (code "60") (name "Net-(U3-IO15)") (class "Default")
      (node (ref "R6") (pin "2") (pinfunction "2_2") (pintype "passive"))
      (node (ref "U3") (pin "16") (pinfunction "IO15_16") (pintype "passive"))
    )
    (net (code "61") (name "Net-(U6-ANT)") (class "Default")
      (node (ref "U6") (pin "9") (pinfunction "ANT_9") (pintype "passive"))
    )
    (net (code "62") (name "Net-(U7-BYPASS)") (class "Default")
      (node (ref "C26") (pin "1") (pinfunction "1_1") (pintype "passive"))
      (node (ref "U7") (pin "2") (pinfunction "BYPASS_2") (pintype "passive"))
      (node (ref "U7") (pin "3") (pinfunction "IN+_3") (pintype "passive"))
    )
    (net (code "63") (name "Net-(U7-IN-)") (class "Default")
      (node (ref "R24") (pin "1") (pinfunction "1_1") (pintype "passive"))
      (node (ref "R7") (pin "1") (pinfunction "1_1") (pintype "passive"))
      (node (ref "R8") (pin "1") (pinfunction "1_1") (pintype "passive"))
      (node (ref "U7") (pin "4") (pinfunction "IN-_4") (pintype "passive"))
    )
    (net (code "64") (name "Net-(U10-VCOM)") (class "Default")
      (node (ref "C29") (pin "2") (pinfunction "2_2") (pintype "passive"))
      (node (ref "U10") (pin "7") (pinfunction "VCOM_7") (pintype "passive"))
    )
    (net (code "65") (name "VCC5") (class "Default")
      (node (ref "C13") (pin "1") (pinfunction "1_1") (pintype "passive"))
      (node (ref "C14") (pin "2") (pinfunction "2_2") (pintype "passive"))
      (node (ref "C17") (pin "2") (pinfunction "2_2") (pintype "passive"))
      (node (ref "C20") (pin "1") (pinfunction "1_1") (pintype "passive"))
      (node (ref "C21") (pin "1") (pinfunction "1_1") (pintype "passive"))
      (node (ref "C23") (pin "1") (pinfunction "1_1") (pintype "passive"))
      (node (ref "C24") (pin "1") (pinfunction "1_1") (pintype "passive"))
      (node (ref "C28") (pin "1") (pinfunction "1_1") (pintype "passive"))
      (node (ref "C36") (pin "2") (pinfunction "2_2") (pintype "passive"))
      (node (ref "C5") (pin "1") (pinfunction "1_1") (pintype "passive"))
      (node (ref "C7") (pin "1") (pinfunction "1_1") (pintype "passive"))
      (node (ref "D11") (pin "2") (pinfunction "2_2") (pintype "passive"))
      (node (ref "D3") (pin "5") (pinfunction "REF_5") (pintype "power_in"))
      (node (ref "J3") (pin "3") (pinfunction "3_3") (pintype "passive"))
      (node (ref "J6") (pin "1") (pinfunction "VCC_1") (pintype "passive"))
      (node (ref "R10") (pin "2") (pinfunction "2_2") (pintype "passive"))
      (node (ref "R11") (pin "2") (pinfunction "2_2") (pintype "passive"))
      (node (ref "R12") (pin "2") (pinfunction "2_2") (pintype "passive"))
      (node (ref "R13") (pin "2") (pinfunction "2_2") (pintype "passive"))
      (node (ref "R14") (pin "2") (pinfunction "2_2") (pintype "passive"))
      (node (ref "R15") (pin "2") (pinfunction "2_2") (pintype "passive"))
      (node (ref "R9") (pin "2") (pinfunction "2_2") (pintype "passive"))
      (node (ref "U10") (pin "12") (pinfunction "VMCU_12") (pintype "passive"))
      (node (ref "U4") (pin "3") (pinfunction "IN_3") (pintype "passive"))
      (node (ref "U5") (pin "3") (pinfunction "IN_3") (pintype "passive"))
      (node (ref "U7") (pin "6") (pinfunction "VDD_6") (pintype "passive"))
      (node (ref "VCC5") (pin "1") (pinfunction "1_1") (pintype "passive"))
    )
    (net (code "66") (name "VCC33") (class "Default")
      (node (ref "C16") (pin "1") (pinfunction "1_1") (pintype "passive"))
      (node (ref "C18") (pin "1") (pinfunction "1_1") (pintype "passive"))
      (node (ref "C19") (pin "1") (pinfunction "1_1") (pintype "passive"))
      (node (ref "C30") (pin "1") (pinfunction "1_1") (pintype "passive"))
      (node (ref "U3") (pin "8") (pinfunction "VCC_8") (pintype "passive"))
      (node (ref "U5") (pin "2") (pinfunction "OUT_2") (pintype "passive"))
      (node (ref "U5") (pin "4") (pinfunction "OUT_4") (pintype "passive"))
      (node (ref "U6") (pin "1") (pinfunction "VDD_1") (pintype "passive"))
      (node (ref "VCC33") (pin "1") (pinfunction "1_1") (pintype "passive"))
    )
    (net (code "67") (name "VDD33") (class "Default")
      (node (ref "C15") (pin "1") (pinfunction "1_1") (pintype "passive"))
      (node (ref "C38") (pin "1") (pinfunction "1_1") (pintype "passive"))
      (node (ref "J4") (pin "1") (pinfunction "1_1") (pintype "passive"))
      (node (ref "R1") (pin "1") (pinfunction "1_1") (pintype "passive"))
      (node (ref "R26") (pin "2") (pinfunction "2_2") (pintype "passive"))
      (node (ref "R30") (pin "2") (pinfunction "2_2") (pintype "passive"))
      (node (ref "R41") (pin "2") (pinfunction "2_2") (pintype "passive"))
      (node (ref "U4") (pin "2") (pinfunction "OUT_2") (pintype "passive"))
      (node (ref "U4") (pin "4") (pinfunction "OUT_4") (pintype "passive"))
      (node (ref "U9") (pin "4") (pinfunction "VDD_4") (pintype "passive"))
      (node (ref "VDD33") (pin "1") (pinfunction "1_1") (pintype "passive"))
    )
    (net (code "68") (name "unconnected-(J6-NC-Pad4)") (class "Default")
      (node (ref "J6") (pin "4") (pinfunction "NC_4") (pintype "passive"))
    )
    (net (code "69") (name "unconnected-(U3-ADC-Pad2)") (class "Default")
      (node (ref "U3") (pin "2") (pinfunction "ADC_2") (pintype "passive"))
    )
    (net (code "70") (name "unconnected-(U3-CS0-Pad9)") (class "Default")
      (node (ref "U3") (pin "9") (pinfunction "CS0_9") (pintype "passive"))
    )
    (net (code "71") (name "unconnected-(U3-IO02-Pad17)") (class "Default")
      (node (ref "U3") (pin "17") (pinfunction "IO02_17") (pintype "passive"))
    )
    (net (code "72") (name "unconnected-(U3-IO04-Pad19)") (class "Default")
      (node (ref "U3") (pin "19") (pinfunction "IO04_19") (pintype "passive"))
    )
    (net (code "73") (name "unconnected-(U3-IO05-Pad20)") (class "Default")
      (node (ref "U3") (pin "20") (pinfunction "IO05_20") (pintype "passive"))
    )
    (net (code "74") (name "unconnected-(U3-IO9-Pad11)") (class "Default")
      (node (ref "U3") (pin "11") (pinfunction "IO9_11") (pintype "passive"))
    )
    (net (code "75") (name "unconnected-(U3-IO10-Pad12)") (class "Default")
      (node (ref "U3") (pin "12") (pinfunction "IO10_12") (pintype "passive"))
    )
    (net (code "76") (name "unconnected-(U3-IO12{slash}MISO-Pad6)") (class "Default")
      (node (ref "U3") (pin "6") (pinfunction "IO12/MISO_6") (pintype "passive"))
    )
    (net (code "77") (name "unconnected-(U3-IO13{slash}MOSI-Pad7)") (class "Default")
      (node (ref "U3") (pin "7") (pinfunction "IO13/MOSI_7") (pintype "passive"))
    )
    (net (code "78") (name "unconnected-(U3-IO14{slash}CLK-Pad5)") (class "Default")
      (node (ref "U3") (pin "5") (pinfunction "IO14/CLK_5") (pintype "passive"))
    )
    (net (code "79") (name "unconnected-(U3-IO16-Pad4)") (class "Default")
      (node (ref "U3") (pin "4") (pinfunction "IO16_4") (pintype "passive"))
    )
    (net (code "80") (name "unconnected-(U3-MISO-Pad10)") (class "Default")
      (node (ref "U3") (pin "10") (pinfunction "MISO_10") (pintype "passive"))
    )
    (net (code "81") (name "unconnected-(U3-MOSI-Pad13)") (class "Default")
      (node (ref "U3") (pin "13") (pinfunction "MOSI_13") (pintype "passive"))
    )
    (net (code "82") (name "unconnected-(U3-SCLK-Pad14)") (class "Default")
      (node (ref "U3") (pin "14") (pinfunction "SCLK_14") (pintype "passive"))
    )
    (net (code "83") (name "unconnected-(U9-nc-Pad5)") (class "Default")
      (node (ref "U9") (pin "5") (pinfunction "nc_5") (pintype "passive"))
    )
    (net (code "84") (name "unconnected-(U9-nc-Pad6)") (class "Default")
      (node (ref "U9") (pin "6") (pinfunction "nc_6") (pintype "passive"))
    )
    (net (code "85") (name "unconnected-(U9-nc-Pad7)") (class "Default")
      (node (ref "U9") (pin "7") (pinfunction "nc_7") (pintype "passive"))
    )
    (net (code "86") (name "unconnected-(U9-nc-Pad8)") (class "Default")
      (node (ref "U9") (pin "8") (pinfunction "nc_8") (pintype "passive"))
    )
    (net (code "87") (name "unconnected-(U10-VPP-Pad16)") (class "Default")
      (node (ref "U10") (pin "16") (pinfunction "VPP_16") (pintype "passive"))
    )
  )
)
